# RFID_reva.net
KiCad netlist of a schematic drawn in EAGLE
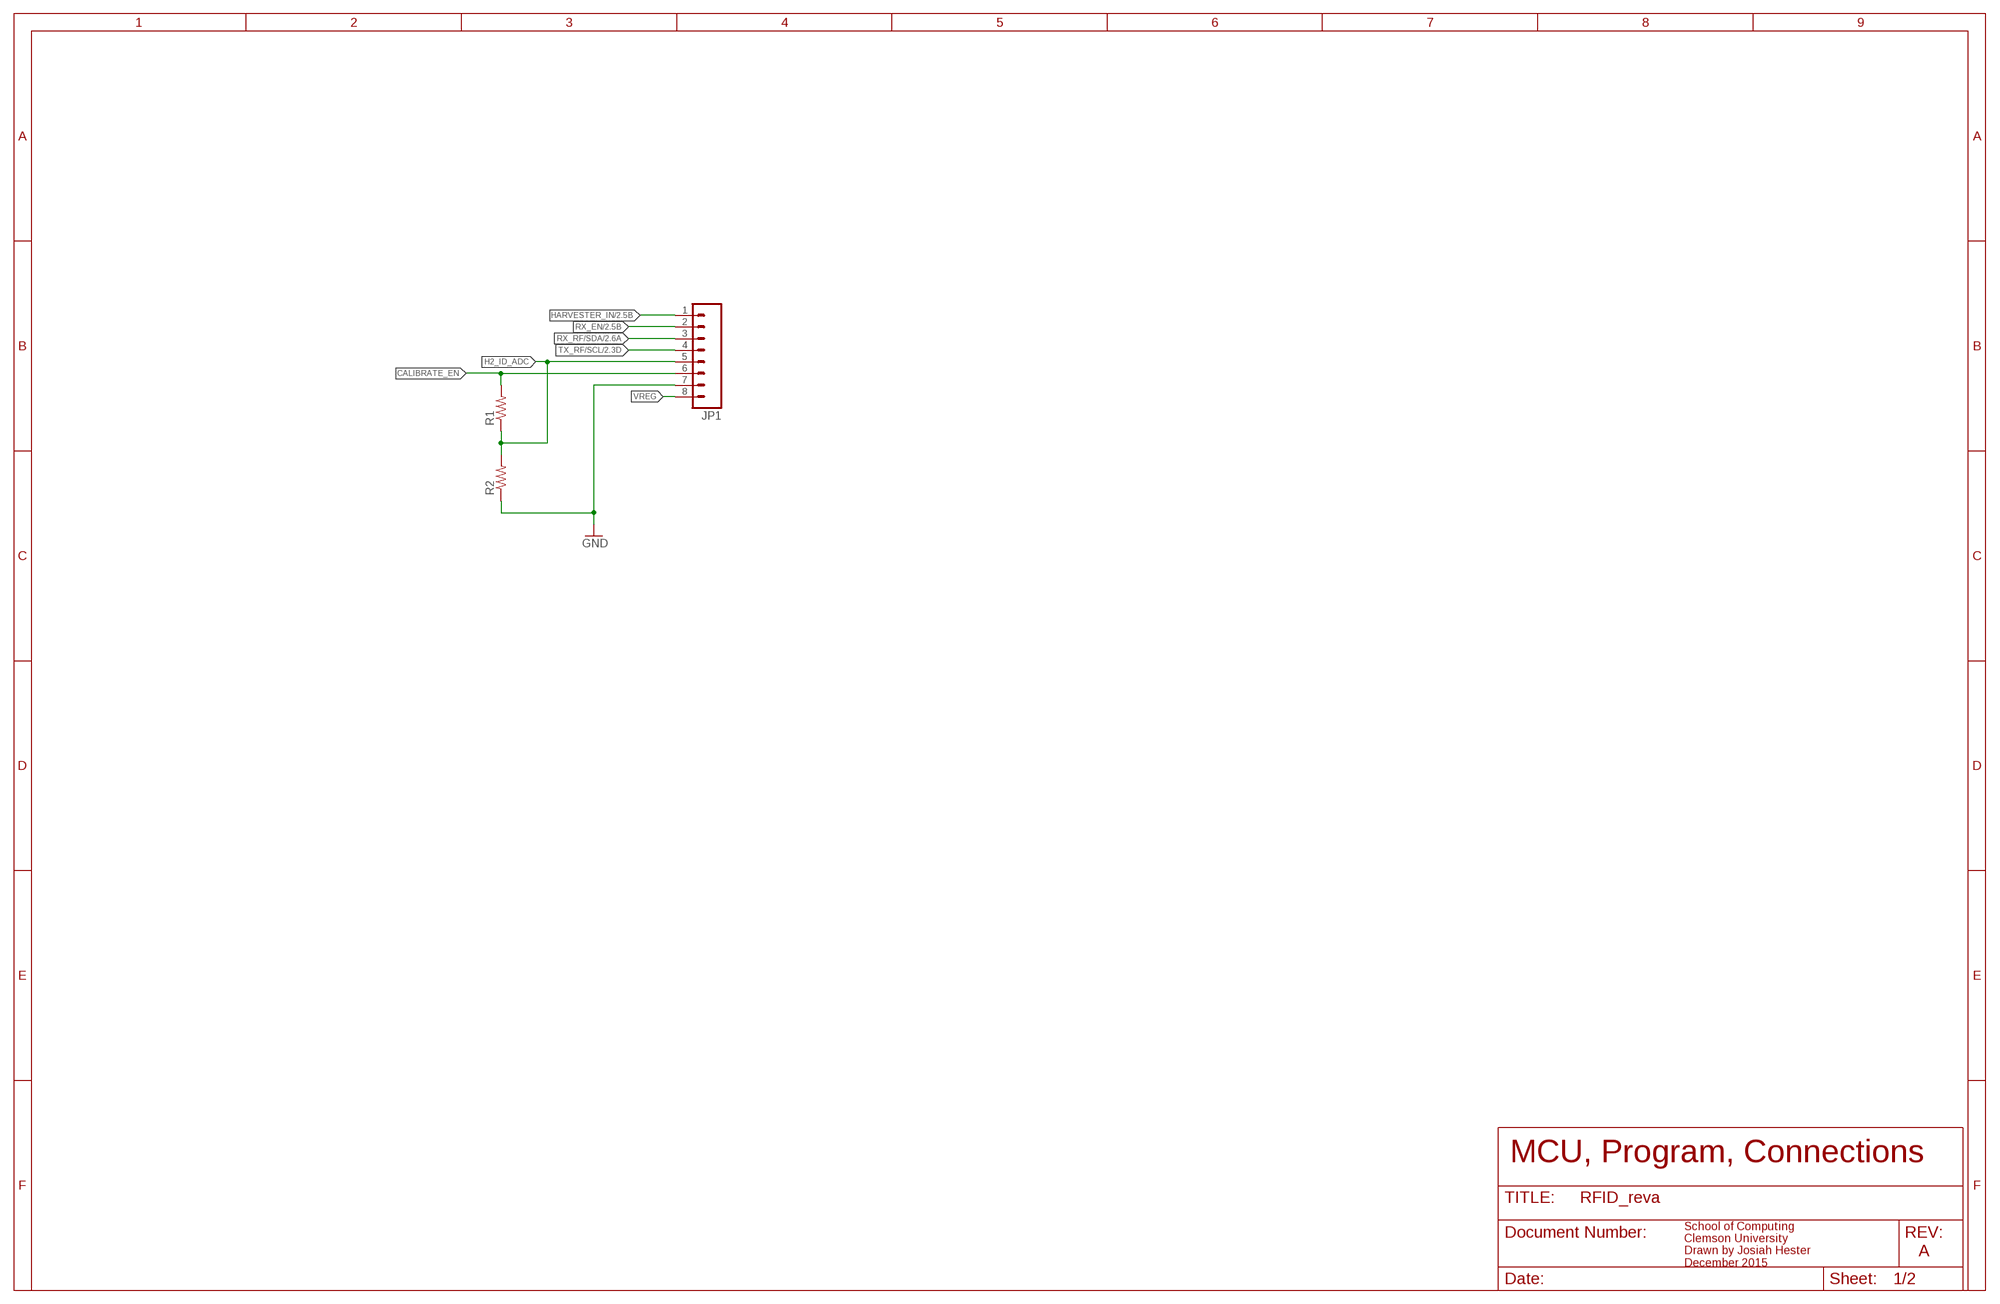
[diagram p0: schematic, sheet 1]
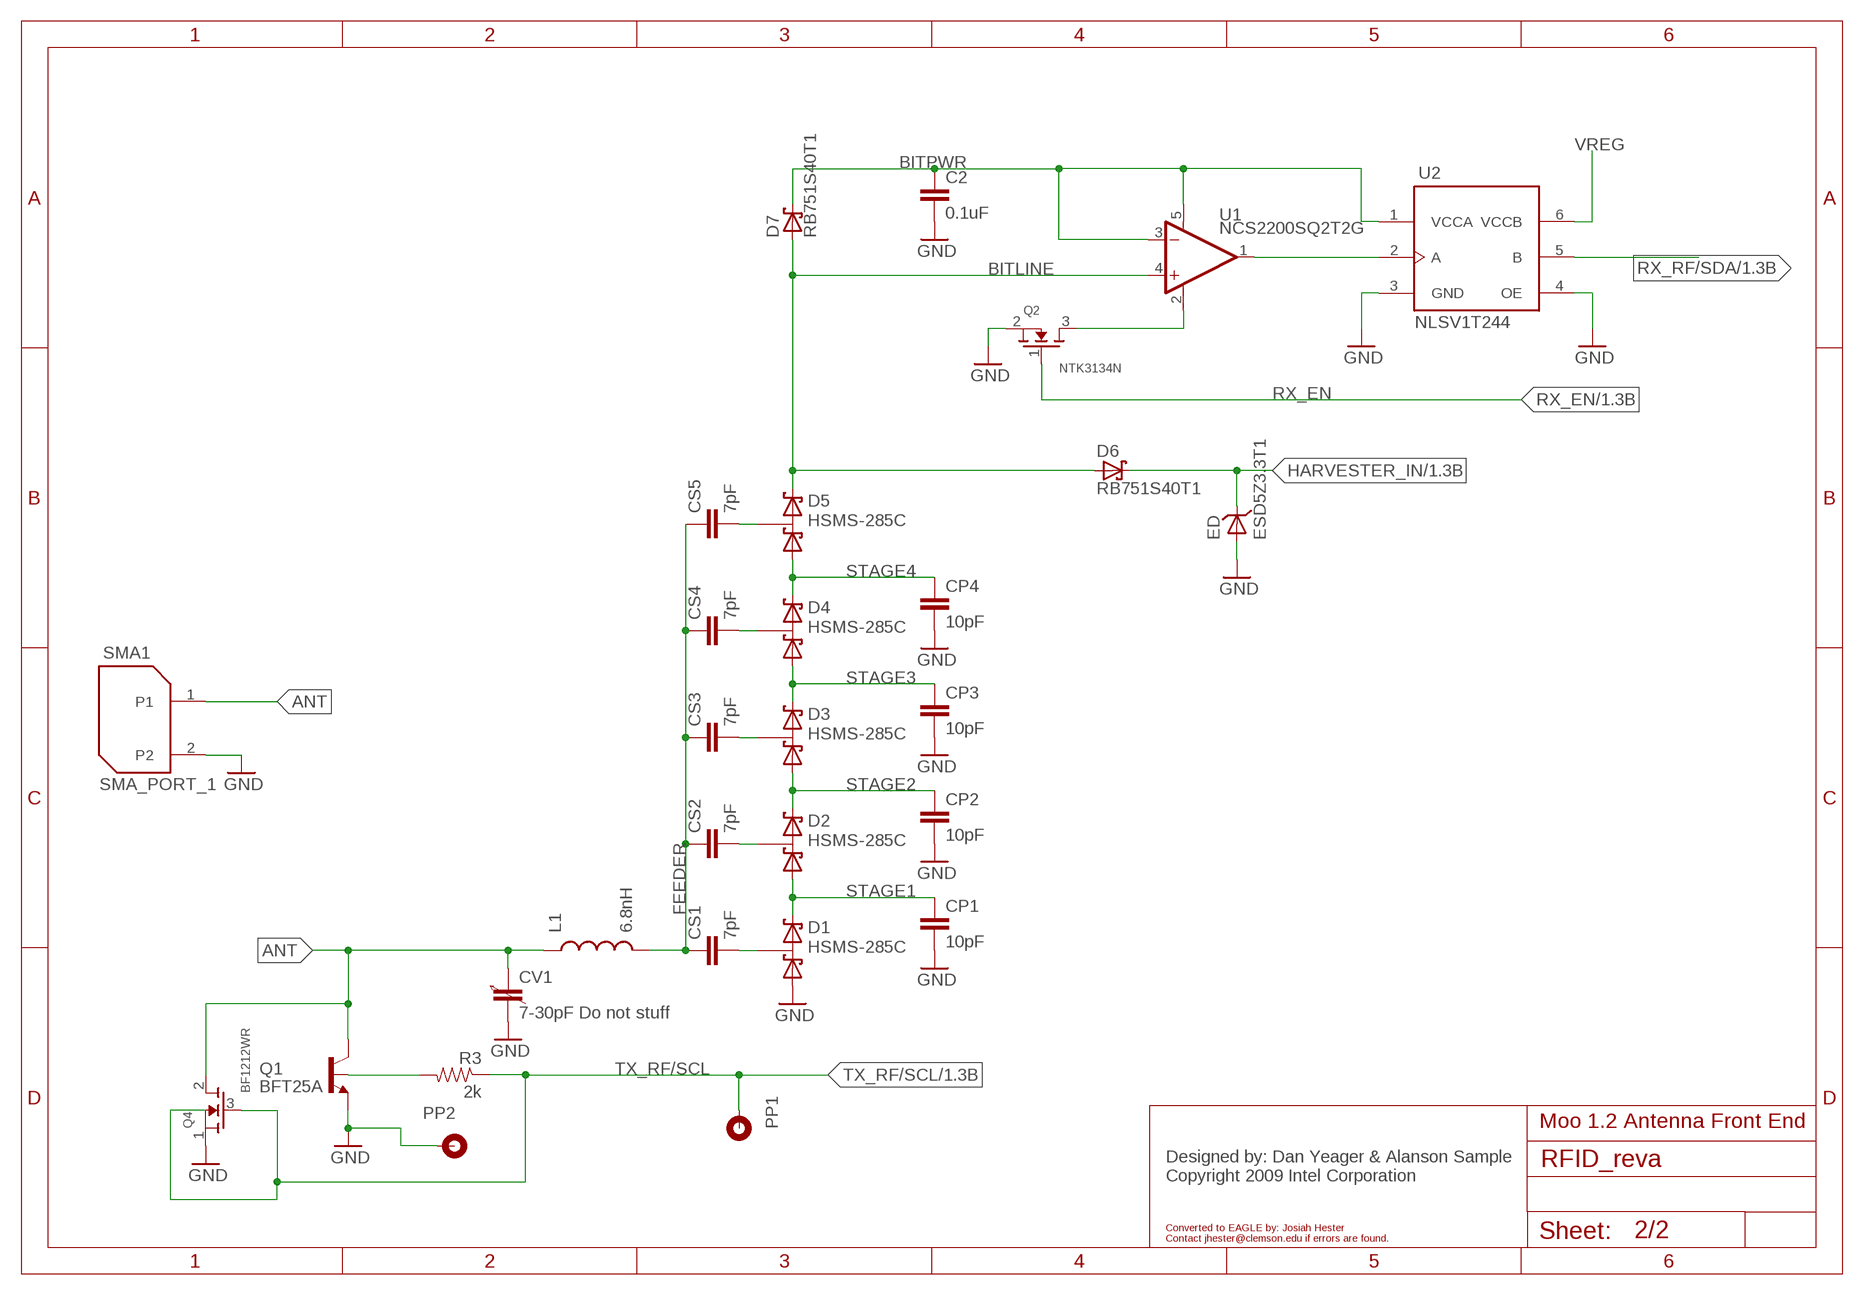
[diagram p1: schematic, sheet 2]

(export (version "E")
  (design (tool "Eeschema 10.0.6"))
  (components
    (comp (ref "JP1")
      (value "M081.27MM")
      (footprint "eagle-import:1X08-1.27MM")
      (libsource (lib "eagle-import") (part "M081.27MM"))
    )
    (comp (ref "R1")
      (value "R-EU0603")
      (footprint "eagle-import:0603")
      (libsource (lib "eagle-import") (part "R-EU0603"))
    )
    (comp (ref "R2")
      (value "R-EU0603")
      (footprint "eagle-import:0603")
      (libsource (lib "eagle-import") (part "R-EU0603"))
    )
    (comp (ref "C2")
      (value "0.1uF")
      (footprint "eagle-import:0402_1PRIMARY")
      (libsource (lib "eagle-import") (part "0402_1"))
    )
    (comp (ref "CP1")
      (value "10pF")
      (footprint "eagle-import:0402_1PRIMARY")
      (libsource (lib "eagle-import") (part "0402_1"))
    )
    (comp (ref "CP2")
      (value "10pF")
      (footprint "eagle-import:0402_1PRIMARY")
      (libsource (lib "eagle-import") (part "0402_1"))
    )
    (comp (ref "CP3")
      (value "10pF")
      (footprint "eagle-import:0402_1PRIMARY")
      (libsource (lib "eagle-import") (part "0402_1"))
    )
    (comp (ref "CP4")
      (value "10pF")
      (footprint "eagle-import:0402_1PRIMARY")
      (libsource (lib "eagle-import") (part "0402_1"))
    )
    (comp (ref "CS1")
      (value "7pF")
      (footprint "eagle-import:0402_1PRIMARY")
      (libsource (lib "eagle-import") (part "0402_1"))
    )
    (comp (ref "CS2")
      (value "7pF")
      (footprint "eagle-import:0402_1PRIMARY")
      (libsource (lib "eagle-import") (part "0402_1"))
    )
    (comp (ref "CS3")
      (value "7pF")
      (footprint "eagle-import:0402_1PRIMARY")
      (libsource (lib "eagle-import") (part "0402_1"))
    )
    (comp (ref "CS4")
      (value "7pF")
      (footprint "eagle-import:0402_1PRIMARY")
      (libsource (lib "eagle-import") (part "0402_1"))
    )
    (comp (ref "CS5")
      (value "7pF")
      (footprint "eagle-import:0402_1PRIMARY")
      (libsource (lib "eagle-import") (part "0402_1"))
    )
    (comp (ref "CV1")
      (value "7-30pF Do not stuff")
      (footprint "eagle-import:VAR-CAP_603_1PRIMARY")
      (libsource (lib "eagle-import") (part "VAR-CAP_603_1"))
    )
    (comp (ref "D1")
      (value "HSMS-285C")
      (footprint "eagle-import:SOT-323,_HSMS-285C_1PRIMARY")
      (libsource (lib "eagle-import") (part "HSMS-285C"))
    )
    (comp (ref "D2")
      (value "HSMS-285C")
      (footprint "eagle-import:SOT-323,_HSMS-285C_1PRIMARY")
      (libsource (lib "eagle-import") (part "HSMS-285C"))
    )
    (comp (ref "D3")
      (value "HSMS-285C")
      (footprint "eagle-import:SOT-323,_HSMS-285C_1PRIMARY")
      (libsource (lib "eagle-import") (part "HSMS-285C"))
    )
    (comp (ref "D4")
      (value "HSMS-285C")
      (footprint "eagle-import:SOT-323,_HSMS-285C_1PRIMARY")
      (libsource (lib "eagle-import") (part "HSMS-285C"))
    )
    (comp (ref "D5")
      (value "HSMS-285C")
      (footprint "eagle-import:SOT-323,_HSMS-285C_1PRIMARY")
      (libsource (lib "eagle-import") (part "HSMS-285C"))
    )
    (comp (ref "D6")
      (value "RB751S40T1")
      (footprint "eagle-import:SOD-523_1PRIMARY")
      (libsource (lib "eagle-import") (part "RB751S40T1"))
    )
    (comp (ref "D7")
      (value "RB751S40T1")
      (footprint "eagle-import:SOD-523_1PRIMARY")
      (libsource (lib "eagle-import") (part "RB751S40T1"))
    )
    (comp (ref "ED")
      (value "ESD5Z3.3T1")
      (footprint "eagle-import:SOD-523_1PRIMARY")
      (libsource (lib "eagle-import") (part "ESD5Z3.3T1"))
    )
    (comp (ref "L1")
      (value "6.8nH")
      (footprint "eagle-import:0603_1PRIMARY")
      (libsource (lib "eagle-import") (part "0603_1"))
    )
    (comp (ref "PP1")
      (value "PROBE_POINT_2")
      (footprint "eagle-import:PROBE_POINT_2PRIMARY")
      (libsource (lib "eagle-import") (part "PROBE_POINT_2"))
    )
    (comp (ref "PP2")
      (value "PROBE_POINT_1")
      (footprint "eagle-import:PROBE_POINT_2PRIMARY")
      (libsource (lib "eagle-import") (part "PROBE_POINT_1"))
    )
    (comp (ref "Q1")
      (value "BFT25A")
      (footprint "eagle-import:SOT-23_1PRIMARY")
      (libsource (lib "eagle-import") (part "BFT25A"))
    )
    (comp (ref "Q2")
      (value "NTK3134N")
      (footprint "eagle-import:SOT723_1PRIMARY")
      (libsource (lib "eagle-import") (part "NTK3134N"))
    )
    (comp (ref "Q4")
      (value "BF1212WR")
      (footprint "eagle-import:SOT343R_1PRIMARY")
      (libsource (lib "eagle-import") (part "BF1212WR"))
    )
    (comp (ref "R3")
      (value "2k")
      (footprint "eagle-import:0402_1PRIMARY")
      (libsource (lib "eagle-import") (part "0402RES"))
    )
    (comp (ref "SMA1")
      (value "SMA_PORT_1")
      (footprint "eagle-import:SMA_PORT_1PRIMARY")
      (libsource (lib "eagle-import") (part "SMA_PORT_1"))
    )
    (comp (ref "U1")
      (value "NCS2200SQ2T2G")
      (footprint "eagle-import:SC70-5_1PRIMARY")
      (libsource (lib "eagle-import") (part "NCS2200SQ2T2G"))
    )
    (comp (ref "U2")
      (value "NLSV1T244")
      (footprint "eagle-import:UDFN6_1PRIMARY")
      (libsource (lib "eagle-import") (part "NLSV1T244"))
    )
  )
  (nets
    (net (code "1") (name "ANT") (class "Default")
      (node (ref "CV1") (pin "1") (pinfunction "1_1") (pintype "passive"))
      (node (ref "L1") (pin "1") (pinfunction "1_1") (pintype "passive"))
      (node (ref "Q1") (pin "3") (pinfunction "C_3") (pintype "passive"))
      (node (ref "Q4") (pin "2") (pinfunction "3_2") (pintype "bidirectional"))
      (node (ref "SMA1") (pin "1") (pinfunction "P1_1") (pintype "bidirectional"))
    )
    (net (code "2") (name "BITLINE") (class "Default")
      (node (ref "D5") (pin "2") (pinfunction "2_2") (pintype "passive"))
      (node (ref "D6") (pin "2") (pinfunction "A_2") (pintype "passive"))
      (node (ref "D7") (pin "2") (pinfunction "A_2") (pintype "passive"))
      (node (ref "U1") (pin "4") (pinfunction "4_4") (pintype "input"))
    )
    (net (code "3") (name "BITPWR") (class "Default")
      (node (ref "C2") (pin "1") (pinfunction "1_1") (pintype "passive"))
      (node (ref "D7") (pin "1") (pinfunction "C_1") (pintype "passive"))
      (node (ref "U1") (pin "3") (pinfunction "3_3") (pintype "input"))
      (node (ref "U1") (pin "5") (pinfunction "5_5") (pintype "input"))
      (node (ref "U2") (pin "1") (pinfunction "VCCA_1") (pintype "bidirectional"))
    )
    (net (code "4") (name "CALIBRATE_EN") (class "Default")
      (node (ref "JP1") (pin "6") (pinfunction "6_6") (pintype "passive"))
      (node (ref "R1") (pin "2") (pinfunction "2_2") (pintype "passive"))
    )
    (net (code "5") (name "FEEDER") (class "Default")
      (node (ref "CS1") (pin "1") (pinfunction "1_1") (pintype "passive"))
      (node (ref "CS2") (pin "1") (pinfunction "1_1") (pintype "passive"))
      (node (ref "CS3") (pin "1") (pinfunction "1_1") (pintype "passive"))
      (node (ref "CS4") (pin "1") (pinfunction "1_1") (pintype "passive"))
      (node (ref "CS5") (pin "1") (pinfunction "1_1") (pintype "passive"))
      (node (ref "L1") (pin "2") (pinfunction "2_2") (pintype "passive"))
    )
    (net (code "6") (name "GND") (class "Default")
      (node (ref "C2") (pin "2") (pinfunction "2_2") (pintype "passive"))
      (node (ref "CP1") (pin "2") (pinfunction "2_2") (pintype "passive"))
      (node (ref "CP2") (pin "2") (pinfunction "2_2") (pintype "passive"))
      (node (ref "CP3") (pin "2") (pinfunction "2_2") (pintype "passive"))
      (node (ref "CP4") (pin "2") (pinfunction "2_2") (pintype "passive"))
      (node (ref "CV1") (pin "2") (pinfunction "2_2") (pintype "passive"))
      (node (ref "D1") (pin "1") (pinfunction "1_1") (pintype "passive"))
      (node (ref "ED") (pin "2") (pinfunction "2_2") (pintype "passive"))
      (node (ref "JP1") (pin "7") (pinfunction "7_7") (pintype "passive"))
      (node (ref "PP2") (pin "1") (pinfunction "1_1") (pintype "bidirectional"))
      (node (ref "Q1") (pin "2") (pinfunction "E_2") (pintype "passive"))
      (node (ref "Q2") (pin "2") (pinfunction "2_2") (pintype "bidirectional"))
      (node (ref "Q4") (pin "1") (pinfunction "2_1") (pintype "bidirectional"))
      (node (ref "R2") (pin "1") (pinfunction "1_1") (pintype "passive"))
      (node (ref "SMA1") (pin "2") (pinfunction "P2_2") (pintype "bidirectional"))
      (node (ref "U2") (pin "3") (pinfunction "GND_3") (pintype "bidirectional"))
      (node (ref "U2") (pin "4") (pinfunction "OE_4") (pintype "bidirectional"))
    )
    (net (code "7") (name "H2_ID_ADC") (class "Default")
      (node (ref "JP1") (pin "5") (pinfunction "5_5") (pintype "passive"))
      (node (ref "R1") (pin "1") (pinfunction "1_1") (pintype "passive"))
      (node (ref "R2") (pin "2") (pinfunction "2_2") (pintype "passive"))
    )
    (net (code "8") (name "HARVESTER_IN") (class "Default")
      (node (ref "D6") (pin "1") (pinfunction "C_1") (pintype "passive"))
      (node (ref "ED") (pin "1") (pinfunction "1_1") (pintype "passive"))
      (node (ref "JP1") (pin "1") (pinfunction "1_1") (pintype "passive"))
    )
    (net (code "9") (name "Net-(CS1-Pad2)") (class "Default")
      (node (ref "CS1") (pin "2") (pinfunction "2_2") (pintype "passive"))
      (node (ref "D1") (pin "3") (pinfunction "3_3") (pintype "passive"))
    )
    (net (code "10") (name "Net-(CS2-Pad2)") (class "Default")
      (node (ref "CS2") (pin "2") (pinfunction "2_2") (pintype "passive"))
      (node (ref "D2") (pin "3") (pinfunction "3_3") (pintype "passive"))
    )
    (net (code "11") (name "Net-(CS3-Pad2)") (class "Default")
      (node (ref "CS3") (pin "2") (pinfunction "2_2") (pintype "passive"))
      (node (ref "D3") (pin "3") (pinfunction "3_3") (pintype "passive"))
    )
    (net (code "12") (name "Net-(CS4-Pad2)") (class "Default")
      (node (ref "CS4") (pin "2") (pinfunction "2_2") (pintype "passive"))
      (node (ref "D4") (pin "3") (pinfunction "3_3") (pintype "passive"))
    )
    (net (code "13") (name "Net-(CS5-Pad2)") (class "Default")
      (node (ref "CS5") (pin "2") (pinfunction "2_2") (pintype "passive"))
      (node (ref "D5") (pin "3") (pinfunction "3_3") (pintype "passive"))
    )
    (net (code "14") (name "Net-(Q1-B)") (class "Default")
      (node (ref "Q1") (pin "1") (pinfunction "B_1") (pintype "passive"))
      (node (ref "R3") (pin "1") (pinfunction "2_1") (pintype "passive"))
    )
    (net (code "15") (name "Net-(Q2-Pad3)") (class "Default")
      (node (ref "Q2") (pin "3") (pinfunction "3_3") (pintype "bidirectional"))
      (node (ref "U1") (pin "2") (pinfunction "2_2") (pintype "input"))
    )
    (net (code "16") (name "Net-(U2-A)") (class "Default")
      (node (ref "U1") (pin "1") (pinfunction "1_1") (pintype "output"))
      (node (ref "U2") (pin "2") (pinfunction "A_2") (pintype "bidirectional"))
    )
    (net (code "17") (name "RX_EN") (class "Default")
      (node (ref "JP1") (pin "2") (pinfunction "2_2") (pintype "passive"))
      (node (ref "Q2") (pin "1") (pinfunction "1_1") (pintype "bidirectional"))
    )
    (net (code "18") (name "RX_RF{slash}SDA") (class "Default")
      (node (ref "JP1") (pin "3") (pinfunction "3_3") (pintype "passive"))
      (node (ref "U2") (pin "5") (pinfunction "B_5") (pintype "output"))
    )
    (net (code "19") (name "STAGE1") (class "Default")
      (node (ref "CP1") (pin "1") (pinfunction "1_1") (pintype "passive"))
      (node (ref "D1") (pin "2") (pinfunction "2_2") (pintype "passive"))
      (node (ref "D2") (pin "1") (pinfunction "1_1") (pintype "passive"))
    )
    (net (code "20") (name "STAGE2") (class "Default")
      (node (ref "CP2") (pin "1") (pinfunction "1_1") (pintype "passive"))
      (node (ref "D2") (pin "2") (pinfunction "2_2") (pintype "passive"))
      (node (ref "D3") (pin "1") (pinfunction "1_1") (pintype "passive"))
    )
    (net (code "21") (name "STAGE3") (class "Default")
      (node (ref "CP3") (pin "1") (pinfunction "1_1") (pintype "passive"))
      (node (ref "D3") (pin "2") (pinfunction "2_2") (pintype "passive"))
      (node (ref "D4") (pin "1") (pinfunction "1_1") (pintype "passive"))
    )
    (net (code "22") (name "STAGE4") (class "Default")
      (node (ref "CP4") (pin "1") (pinfunction "1_1") (pintype "passive"))
      (node (ref "D4") (pin "2") (pinfunction "2_2") (pintype "passive"))
      (node (ref "D5") (pin "1") (pinfunction "1_1") (pintype "passive"))
    )
    (net (code "23") (name "TX_RF{slash}SCL") (class "Default")
      (node (ref "JP1") (pin "4") (pinfunction "4_4") (pintype "passive"))
      (node (ref "PP1") (pin "1") (pinfunction "1_1") (pintype "bidirectional"))
      (node (ref "Q4") (pin "3") (pinfunction "1_3") (pintype "bidirectional"))
      (node (ref "Q4") (pin "4") (pinfunction "4_4") (pintype "bidirectional"))
      (node (ref "R3") (pin "2") (pinfunction "1_2") (pintype "passive"))
    )
    (net (code "24") (name "VREG") (class "Default")
      (node (ref "JP1") (pin "8") (pinfunction "8_8") (pintype "passive"))
      (node (ref "U2") (pin "6") (pinfunction "VCCB_6") (pintype "bidirectional"))
    )
  )
)
